# emi_filter_ch1_b.net
KiCad netlist of a schematic drawn in Altium Designer
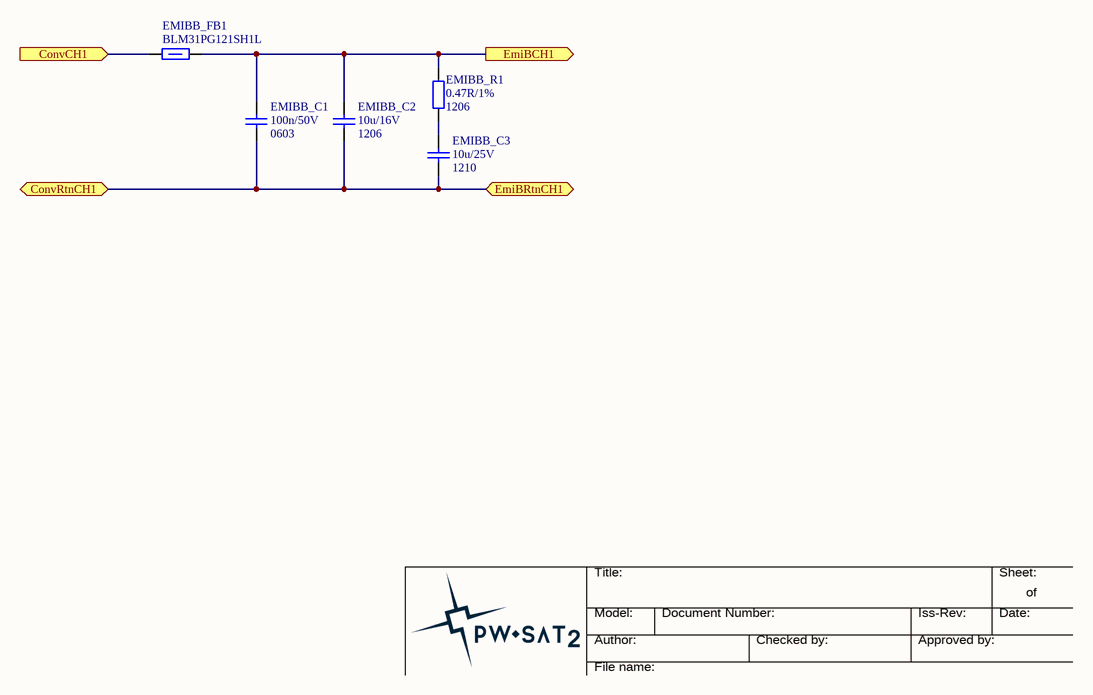
[diagram p0: emi_filter_ch1_b.SchDoc]

(export (version "E")
  (design (tool "Eeschema 10.0.6"))
  (components
    (comp (ref "EMIBB_C1")
      (value "100n/50V")
      (footprint "SMD_Capacitor_0603")
      (description "Ceramic Cap Kemet COTS 100n/50V X7R 0603")
      (fields
        (field (name "MANUFACTURER") "Kemet")
        (field (name "MANUFACTURERPARTNUMBER") "C0603T104K5RALTU")
        (field (name "PACKAGE") "0603")
      )
      (libsource (lib "capacitors") (part "Cer_C0603T104K5RALTU"))
    )
    (comp (ref "EMIBB_C2")
      (value "10u/16V")
      (footprint "SMD_Capacitor_1206")
      (description "Ceramic Cap Kemet COTS 10u/16V X7R 1206")
      (fields
        (field (name "MANUFACTURERPARTNUMBER") "C1206T106K4RACTU")
        (field (name "MANUFACTURER") "Kemet")
        (field (name "PACKGE") "1206")
      )
      (libsource (lib "capacitors") (part "Cer_C1206T106K4RACTU"))
    )
    (comp (ref "EMIBB_C3")
      (value "10u/25V")
      (footprint "SMD_Capacitor_1210")
      (description "Ceramic Cap Murata Automotive 10u/25V X7R 1210")
      (fields
        (field (name "MANUFACTURER") "Murata")
        (field (name "MANUFACTURERPARTNUMBER") "GCJ32ER71E106KA12L")
        (field (name "PACKAGE") "1210")
      )
      (libsource (lib "capacitors") (part "Cer_GCJ32ER71E106KA12L"))
    )
    (comp (ref "EMIBB_FB1")
      (value "120R/100MHz")
      (footprint "SMD_FerriteBead_1206")
      (description "Ferrite bead, 1206, 0.02HM, 3.5A.")
      (fields (field (name "MANUFACTURER") "Murata") (field (name "MANUFACTURERPARTNUMBER") "BLM31PG121SH1L"))
      (libsource (lib "inductors") (part "BLM31PG121SH1L"))
    )
    (comp (ref "EMIBB_R1")
      (value "0.47R/1%")
      (footprint "SMD_Resistor_1206")
      (description "Panasonic Resistor 0.47R 1% 1206 330mW")
      (fields
        (field (name "MANUFACTURERPARTNUMBER") "ERJ-8BQFR47V")
        (field (name "MANUFACTURER") "Panasonic")
        (field (name "PACKAGE") "1206")
      )
      (libsource (lib "resistors") (part "ERJ-8BQFR47V"))
    )
  )
  (nets
    (net (code "1") (name "/ConvCH1") (class "Default")
      (node (ref "EMIBB_FB1") (pin "2") (pinfunction "2_2") (pintype "passive"))
    )
    (net (code "2") (name "/ConvRtnCH1") (class "Default")
      (node (ref "EMIBB_C1") (pin "2") (pinfunction "2_2") (pintype "passive"))
      (node (ref "EMIBB_C2") (pin "2") (pinfunction "2_2") (pintype "passive"))
      (node (ref "EMIBB_C3") (pin "2") (pinfunction "2_2") (pintype "passive"))
    )
    (net (code "3") (name "/EmiBCH1") (class "Default")
      (node (ref "EMIBB_C1") (pin "1") (pinfunction "1_1") (pintype "passive"))
      (node (ref "EMIBB_C2") (pin "1") (pinfunction "1_1") (pintype "passive"))
      (node (ref "EMIBB_FB1") (pin "1") (pinfunction "1_1") (pintype "passive"))
      (node (ref "EMIBB_R1") (pin "2") (pinfunction "2_2") (pintype "passive"))
    )
    (net (code "4") (name "Net-(EMIBB_C3-Pad1)") (class "Default")
      (node (ref "EMIBB_C3") (pin "1") (pinfunction "1_1") (pintype "passive"))
      (node (ref "EMIBB_R1") (pin "1") (pinfunction "1_1") (pintype "passive"))
    )
  )
)
